# rc2014_nsc800.net
KiCad netlist of a schematic drawn in EAGLE
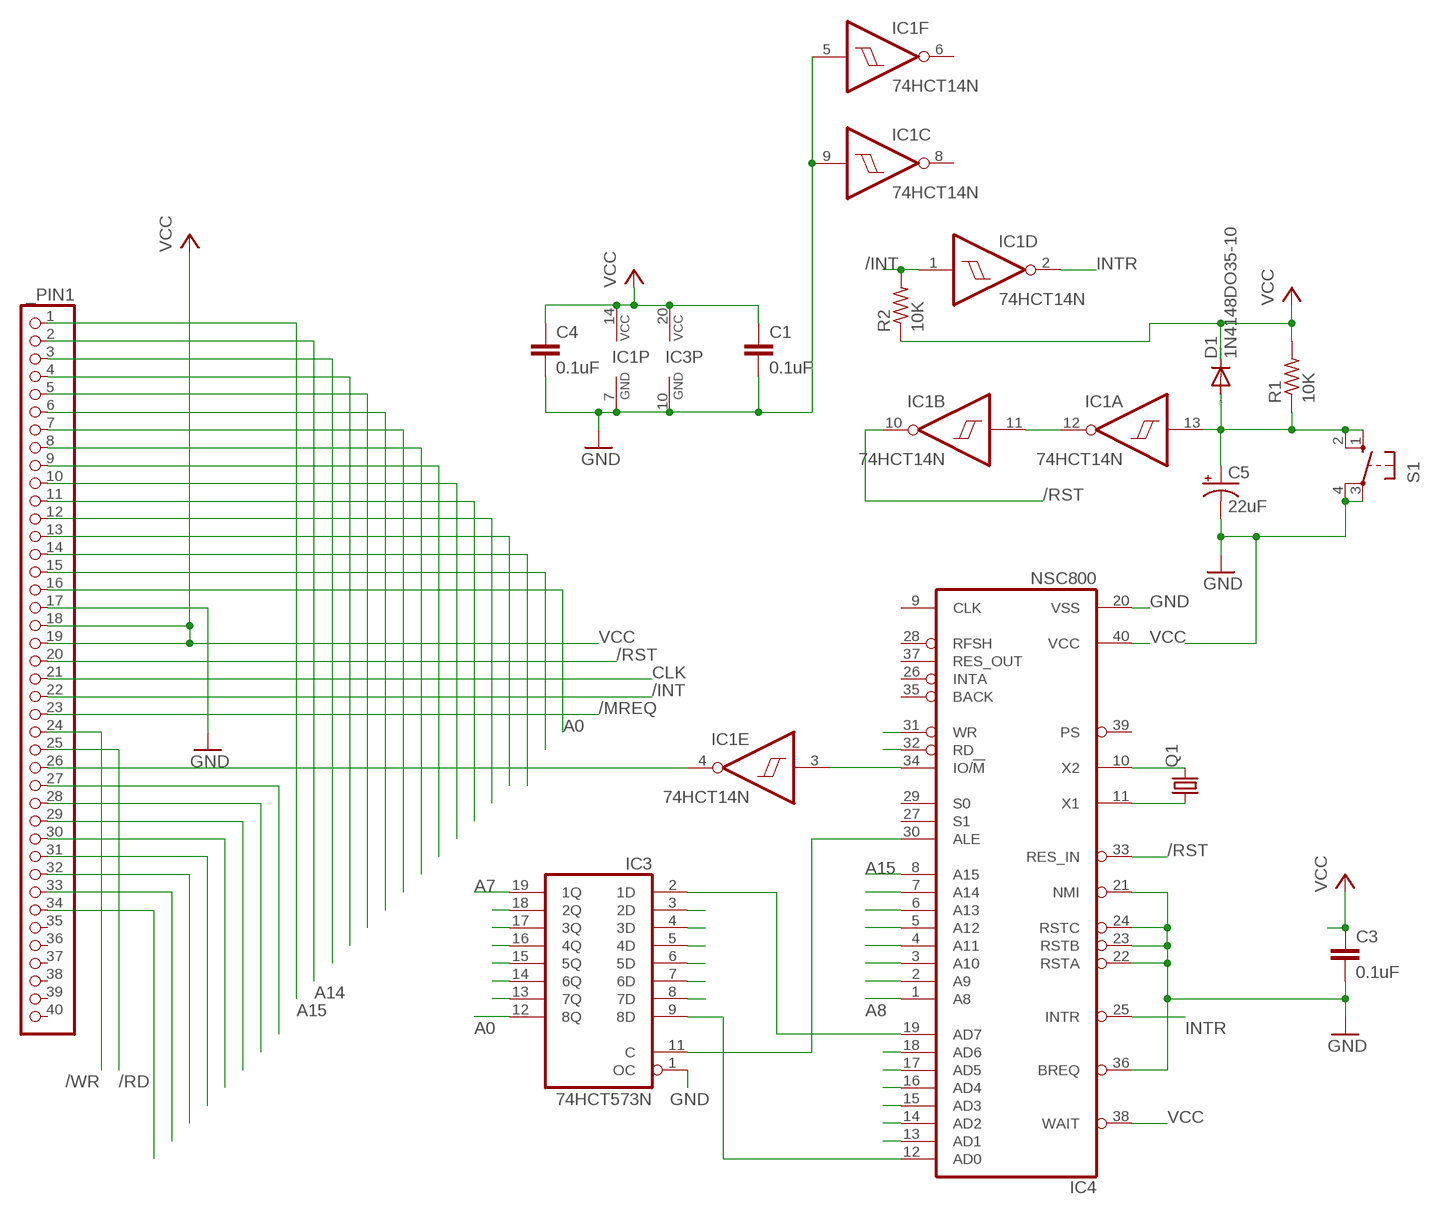
[diagram p0: schematic, sheet 1]

(export (version "E")
  (design (tool "Eeschema 10.0.6"))
  (components
    (comp (ref "C1")
      (value "0.1uF")
      (footprint "eagle-import:C050-024X044")
      (libsource (lib "eagle-import") (part "C-EU050-024X044"))
    )
    (comp (ref "C3")
      (value "0.1uF")
      (footprint "eagle-import:C050-024X044")
      (libsource (lib "eagle-import") (part "C-EU050-024X044"))
    )
    (comp (ref "C4")
      (value "0.1uF")
      (footprint "eagle-import:C050-024X044")
      (libsource (lib "eagle-import") (part "C-EU050-024X044"))
    )
    (comp (ref "C5")
      (value "22uF")
      (footprint "eagle-import:TAP5-80")
      (libsource (lib "eagle-import") (part "CPOL-USTAP5-80"))
    )
    (comp (ref "D1")
      (value "1N4148DO35-10")
      (footprint "eagle-import:DO35-10")
      (libsource (lib "eagle-import") (part "1N4148DO35-10"))
    )
    (comp (ref "IC1")
      (value "74HCT14N")
      (footprint "eagle-import:DIL14")
      (libsource (lib "eagle-import") (part "7414NHCT"))
    )
    (comp (ref "IC3")
      (value "74HCT573N")
      (footprint "eagle-import:DIL20")
      (libsource (lib "eagle-import") (part "74573NHCT"))
    )
    (comp (ref "IC4")
      (value "NSC800")
      (footprint "eagle-import:DIL40")
      (libsource (lib "eagle-import") (part "NSC800"))
    )
    (comp (ref "Q1")
      (value "CRYSTALHC49S")
      (footprint "eagle-import:HC49_S")
      (libsource (lib "eagle-import") (part "CRYSTALHC49S"))
    )
    (comp (ref "R1")
      (value "10K")
      (footprint "eagle-import:0207_10")
      (libsource (lib "eagle-import") (part "R-US_0207/10"))
    )
    (comp (ref "R2")
      (value "10K")
      (footprint "eagle-import:0207_10")
      (libsource (lib "eagle-import") (part "R-US_0207/10"))
    )
    (comp (ref "S1")
      (value "10-XX")
      (footprint "eagle-import:B3F-10XX")
      (fields (field (name "MPN") "B3F-1000"))
      (libsource (lib "eagle-import") (part "10-XX"))
    )
    (comp (ref "_PIN1")
      (value "PINHD-1X40")
      (footprint "eagle-import:1X40")
      (libsource (lib "eagle-import") (part "PINHD-1X40"))
    )
  )
  (nets
    (net (code "1") (name "/A0") (class "Default")
      (node (ref "IC3") (pin "12") (pinfunction "8Q_12") (pintype "tri_state"))
      (node (ref "_PIN1") (pin "16") (pinfunction "16_16") (pintype "passive"))
    )
    (net (code "2") (name "/A1") (class "Default")
      (node (ref "IC3") (pin "13") (pinfunction "7Q_13") (pintype "tri_state"))
      (node (ref "_PIN1") (pin "15") (pinfunction "15_15") (pintype "passive"))
    )
    (net (code "3") (name "/A2") (class "Default")
      (node (ref "IC3") (pin "14") (pinfunction "6Q_14") (pintype "tri_state"))
      (node (ref "_PIN1") (pin "14") (pinfunction "14_14") (pintype "passive"))
    )
    (net (code "4") (name "/A3") (class "Default")
      (node (ref "IC3") (pin "15") (pinfunction "5Q_15") (pintype "tri_state"))
      (node (ref "_PIN1") (pin "13") (pinfunction "13_13") (pintype "passive"))
    )
    (net (code "5") (name "/A4") (class "Default")
      (node (ref "IC3") (pin "16") (pinfunction "4Q_16") (pintype "tri_state"))
      (node (ref "_PIN1") (pin "12") (pinfunction "12_12") (pintype "passive"))
    )
    (net (code "6") (name "/A5") (class "Default")
      (node (ref "IC3") (pin "17") (pinfunction "3Q_17") (pintype "tri_state"))
      (node (ref "_PIN1") (pin "11") (pinfunction "11_11") (pintype "passive"))
    )
    (net (code "7") (name "/A6") (class "Default")
      (node (ref "IC3") (pin "18") (pinfunction "2Q_18") (pintype "tri_state"))
      (node (ref "_PIN1") (pin "10") (pinfunction "10_10") (pintype "passive"))
    )
    (net (code "8") (name "/A7") (class "Default")
      (node (ref "IC3") (pin "19") (pinfunction "1Q_19") (pintype "tri_state"))
      (node (ref "_PIN1") (pin "9") (pinfunction "9_9") (pintype "passive"))
    )
    (net (code "9") (name "/A8") (class "Default")
      (node (ref "IC4") (pin "1") (pinfunction "A8_1") (pintype "output"))
      (node (ref "_PIN1") (pin "8") (pinfunction "8_8") (pintype "passive"))
    )
    (net (code "10") (name "/A9") (class "Default")
      (node (ref "IC4") (pin "2") (pinfunction "A9_2") (pintype "output"))
      (node (ref "_PIN1") (pin "7") (pinfunction "7_7") (pintype "passive"))
    )
    (net (code "11") (name "/A10") (class "Default")
      (node (ref "IC4") (pin "3") (pinfunction "A10_3") (pintype "output"))
      (node (ref "_PIN1") (pin "6") (pinfunction "6_6") (pintype "passive"))
    )
    (net (code "12") (name "/A11") (class "Default")
      (node (ref "IC4") (pin "4") (pinfunction "A11_4") (pintype "output"))
      (node (ref "_PIN1") (pin "5") (pinfunction "5_5") (pintype "passive"))
    )
    (net (code "13") (name "/A12") (class "Default")
      (node (ref "IC4") (pin "5") (pinfunction "A12_5") (pintype "output"))
      (node (ref "_PIN1") (pin "4") (pinfunction "4_4") (pintype "passive"))
    )
    (net (code "14") (name "/A13") (class "Default")
      (node (ref "IC4") (pin "6") (pinfunction "A13_6") (pintype "output"))
      (node (ref "_PIN1") (pin "3") (pinfunction "3_3") (pintype "passive"))
    )
    (net (code "15") (name "/A14") (class "Default")
      (node (ref "IC4") (pin "7") (pinfunction "A14_7") (pintype "output"))
      (node (ref "_PIN1") (pin "2") (pinfunction "2_2") (pintype "passive"))
    )
    (net (code "16") (name "/A15") (class "Default")
      (node (ref "IC4") (pin "8") (pinfunction "A15_8") (pintype "output"))
      (node (ref "_PIN1") (pin "1") (pinfunction "1_1") (pintype "passive"))
    )
    (net (code "17") (name "/CLK") (class "Default")
      (node (ref "_PIN1") (pin "21") (pinfunction "21_21") (pintype "passive"))
    )
    (net (code "18") (name "/D0") (class "Default")
      (node (ref "IC3") (pin "9") (pinfunction "8D_9") (pintype "input"))
      (node (ref "IC4") (pin "12") (pinfunction "AD0_12") (pintype "bidirectional"))
      (node (ref "_PIN1") (pin "27") (pinfunction "27_27") (pintype "passive"))
    )
    (net (code "19") (name "/D1") (class "Default")
      (node (ref "IC3") (pin "8") (pinfunction "7D_8") (pintype "input"))
      (node (ref "IC4") (pin "13") (pinfunction "AD1_13") (pintype "bidirectional"))
      (node (ref "_PIN1") (pin "28") (pinfunction "28_28") (pintype "passive"))
    )
    (net (code "20") (name "/D2") (class "Default")
      (node (ref "IC3") (pin "7") (pinfunction "6D_7") (pintype "input"))
      (node (ref "IC4") (pin "14") (pinfunction "AD2_14") (pintype "bidirectional"))
      (node (ref "_PIN1") (pin "29") (pinfunction "29_29") (pintype "passive"))
    )
    (net (code "21") (name "/D3") (class "Default")
      (node (ref "IC3") (pin "6") (pinfunction "5D_6") (pintype "input"))
      (node (ref "IC4") (pin "15") (pinfunction "AD3_15") (pintype "bidirectional"))
      (node (ref "_PIN1") (pin "30") (pinfunction "30_30") (pintype "passive"))
    )
    (net (code "22") (name "/D4") (class "Default")
      (node (ref "IC3") (pin "5") (pinfunction "4D_5") (pintype "input"))
      (node (ref "IC4") (pin "16") (pinfunction "AD4_16") (pintype "bidirectional"))
      (node (ref "_PIN1") (pin "31") (pinfunction "31_31") (pintype "passive"))
    )
    (net (code "23") (name "/D5") (class "Default")
      (node (ref "IC3") (pin "4") (pinfunction "3D_4") (pintype "input"))
      (node (ref "IC4") (pin "17") (pinfunction "AD5_17") (pintype "bidirectional"))
      (node (ref "_PIN1") (pin "32") (pinfunction "32_32") (pintype "passive"))
    )
    (net (code "24") (name "/D6") (class "Default")
      (node (ref "IC3") (pin "3") (pinfunction "2D_3") (pintype "input"))
      (node (ref "IC4") (pin "18") (pinfunction "AD6_18") (pintype "bidirectional"))
      (node (ref "_PIN1") (pin "33") (pinfunction "33_33") (pintype "passive"))
    )
    (net (code "25") (name "/D7") (class "Default")
      (node (ref "IC3") (pin "2") (pinfunction "1D_2") (pintype "input"))
      (node (ref "IC4") (pin "19") (pinfunction "AD7_19") (pintype "bidirectional"))
      (node (ref "_PIN1") (pin "34") (pinfunction "34_34") (pintype "passive"))
    )
    (net (code "26") (name "/INTR") (class "Default")
      (node (ref "IC1") (pin "2") (pinfunction "O_2") (pintype "output"))
      (node (ref "IC4") (pin "25") (pinfunction "INTR_25") (pintype "input"))
    )
    (net (code "27") (name "/{slash}INT") (class "Default")
      (node (ref "IC1") (pin "1") (pinfunction "I_1") (pintype "input"))
      (node (ref "R2") (pin "2") (pinfunction "2_2") (pintype "passive"))
      (node (ref "_PIN1") (pin "22") (pinfunction "22_22") (pintype "passive"))
    )
    (net (code "28") (name "/{slash}MREQ") (class "Default")
      (node (ref "IC1") (pin "3") (pinfunction "I_3") (pintype "input"))
      (node (ref "IC4") (pin "34") (pinfunction "IO/~{M}_34") (pintype "output"))
      (node (ref "_PIN1") (pin "23") (pinfunction "23_23") (pintype "passive"))
    )
    (net (code "29") (name "/{slash}RD") (class "Default")
      (node (ref "IC4") (pin "32") (pinfunction "RD_32") (pintype "output"))
      (node (ref "_PIN1") (pin "25") (pinfunction "25_25") (pintype "passive"))
    )
    (net (code "30") (name "/{slash}RST") (class "Default")
      (node (ref "IC1") (pin "10") (pinfunction "O_10") (pintype "output"))
      (node (ref "IC4") (pin "33") (pinfunction "RES_IN_33") (pintype "input"))
      (node (ref "_PIN1") (pin "20") (pinfunction "20_20") (pintype "passive"))
    )
    (net (code "31") (name "/{slash}WR") (class "Default")
      (node (ref "IC4") (pin "31") (pinfunction "WR_31") (pintype "output"))
      (node (ref "_PIN1") (pin "24") (pinfunction "24_24") (pintype "passive"))
    )
    (net (code "32") (name "GND") (class "Default")
      (node (ref "C1") (pin "2") (pinfunction "2_2") (pintype "passive"))
      (node (ref "C3") (pin "2") (pinfunction "2_2") (pintype "passive"))
      (node (ref "C4") (pin "2") (pinfunction "2_2") (pintype "passive"))
      (node (ref "C5") (pin "-") (pinfunction "-_-") (pintype "passive"))
      (node (ref "IC1") (pin "5") (pinfunction "I_5") (pintype "input"))
      (node (ref "IC1") (pin "7") (pinfunction "GND_7") (pintype "power_in"))
      (node (ref "IC1") (pin "9") (pinfunction "I_9") (pintype "input"))
      (node (ref "IC3") (pin "1") (pinfunction "OC_1") (pintype "input"))
      (node (ref "IC3") (pin "10") (pinfunction "GND_10") (pintype "power_in"))
      (node (ref "IC4") (pin "20") (pinfunction "VSS_20") (pintype "power_in"))
      (node (ref "IC4") (pin "21") (pinfunction "NMI_21") (pintype "input"))
      (node (ref "IC4") (pin "22") (pinfunction "RSTA_22") (pintype "input"))
      (node (ref "IC4") (pin "23") (pinfunction "RSTB_23") (pintype "input"))
      (node (ref "IC4") (pin "24") (pinfunction "RSTC_24") (pintype "input"))
      (node (ref "IC4") (pin "36") (pinfunction "BREQ_36") (pintype "input"))
      (node (ref "S1") (pin "3") (pinfunction "P_3") (pintype "passive"))
      (node (ref "S1") (pin "4") (pinfunction "P1_4") (pintype "passive"))
      (node (ref "_PIN1") (pin "17") (pinfunction "17_17") (pintype "passive"))
    )
    (net (code "33") (name "Net-(IC1A-I)") (class "Default")
      (node (ref "C5") (pin "+") (pinfunction "+_+") (pintype "passive"))
      (node (ref "D1") (pin "A") (pinfunction "A_A") (pintype "passive"))
      (node (ref "IC1") (pin "13") (pinfunction "I_13") (pintype "input"))
      (node (ref "R1") (pin "1") (pinfunction "1_1") (pintype "passive"))
      (node (ref "S1") (pin "1") (pinfunction "S_1") (pintype "passive"))
      (node (ref "S1") (pin "2") (pinfunction "S1_2") (pintype "passive"))
    )
    (net (code "34") (name "Net-(IC1A-O)") (class "Default")
      (node (ref "IC1") (pin "11") (pinfunction "I_11") (pintype "input"))
      (node (ref "IC1") (pin "12") (pinfunction "O_12") (pintype "output"))
    )
    (net (code "35") (name "Net-(IC1E-O)") (class "Default")
      (node (ref "IC1") (pin "4") (pinfunction "O_4") (pintype "output"))
      (node (ref "_PIN1") (pin "26") (pinfunction "26_26") (pintype "passive"))
    )
    (net (code "36") (name "Net-(IC3A-C)") (class "Default")
      (node (ref "IC3") (pin "11") (pinfunction "C_11") (pintype "input"))
      (node (ref "IC4") (pin "30") (pinfunction "ALE_30") (pintype "output"))
    )
    (net (code "37") (name "Net-(IC4-X1)") (class "Default")
      (node (ref "IC4") (pin "11") (pinfunction "X1_11") (pintype "input"))
      (node (ref "Q1") (pin "1") (pinfunction "1_1") (pintype "passive"))
    )
    (net (code "38") (name "Net-(IC4-X2)") (class "Default")
      (node (ref "IC4") (pin "10") (pinfunction "X2_10") (pintype "input"))
      (node (ref "Q1") (pin "2") (pinfunction "2_2") (pintype "passive"))
    )
    (net (code "39") (name "VCC") (class "Default")
      (node (ref "C1") (pin "1") (pinfunction "1_1") (pintype "passive"))
      (node (ref "C3") (pin "1") (pinfunction "1_1") (pintype "passive"))
      (node (ref "C4") (pin "1") (pinfunction "1_1") (pintype "passive"))
      (node (ref "D1") (pin "C") (pinfunction "C_C") (pintype "passive"))
      (node (ref "IC1") (pin "14") (pinfunction "VCC_14") (pintype "power_in"))
      (node (ref "IC3") (pin "20") (pinfunction "VCC_20") (pintype "power_in"))
      (node (ref "IC4") (pin "38") (pinfunction "WAIT_38") (pintype "input"))
      (node (ref "IC4") (pin "40") (pinfunction "VCC_40") (pintype "power_in"))
      (node (ref "R1") (pin "2") (pinfunction "2_2") (pintype "passive"))
      (node (ref "R2") (pin "1") (pinfunction "1_1") (pintype "passive"))
      (node (ref "_PIN1") (pin "18") (pinfunction "18_18") (pintype "passive"))
      (node (ref "_PIN1") (pin "19") (pinfunction "19_19") (pintype "passive"))
    )
    (net (code "40") (name "unconnected-(IC1C-O-Pad8)") (class "Default")
      (node (ref "IC1") (pin "8") (pinfunction "O_8") (pintype "output"))
    )
    (net (code "41") (name "unconnected-(IC1F-O-Pad6)") (class "Default")
      (node (ref "IC1") (pin "6") (pinfunction "O_6") (pintype "output"))
    )
    (net (code "42") (name "unconnected-(IC4-BACK-Pad35)") (class "Default")
      (node (ref "IC4") (pin "35") (pinfunction "BACK_35") (pintype "output"))
    )
    (net (code "43") (name "unconnected-(IC4-CLK-Pad9)") (class "Default")
      (node (ref "IC4") (pin "9") (pinfunction "CLK_9") (pintype "output"))
    )
    (net (code "44") (name "unconnected-(IC4-INTA-Pad26)") (class "Default")
      (node (ref "IC4") (pin "26") (pinfunction "INTA_26") (pintype "output"))
    )
    (net (code "45") (name "unconnected-(IC4-PS-Pad39)") (class "Default")
      (node (ref "IC4") (pin "39") (pinfunction "PS_39") (pintype "input"))
    )
    (net (code "46") (name "unconnected-(IC4-RES_OUT-Pad37)") (class "Default")
      (node (ref "IC4") (pin "37") (pinfunction "RES_OUT_37") (pintype "output"))
    )
    (net (code "47") (name "unconnected-(IC4-RFSH-Pad28)") (class "Default")
      (node (ref "IC4") (pin "28") (pinfunction "RFSH_28") (pintype "output"))
    )
    (net (code "48") (name "unconnected-(IC4-S0-Pad29)") (class "Default")
      (node (ref "IC4") (pin "29") (pinfunction "S0_29") (pintype "output"))
    )
    (net (code "49") (name "unconnected-(IC4-S1-Pad27)") (class "Default")
      (node (ref "IC4") (pin "27") (pinfunction "S1_27") (pintype "output"))
    )
    (net (code "50") (name "unconnected-(_PIN1-Pad35)") (class "Default")
      (node (ref "_PIN1") (pin "35") (pinfunction "35_35") (pintype "passive"))
    )
    (net (code "51") (name "unconnected-(_PIN1-Pad36)") (class "Default")
      (node (ref "_PIN1") (pin "36") (pinfunction "36_36") (pintype "passive"))
    )
    (net (code "52") (name "unconnected-(_PIN1-Pad37)") (class "Default")
      (node (ref "_PIN1") (pin "37") (pinfunction "37_37") (pintype "passive"))
    )
    (net (code "53") (name "unconnected-(_PIN1-Pad38)") (class "Default")
      (node (ref "_PIN1") (pin "38") (pinfunction "38_38") (pintype "passive"))
    )
    (net (code "54") (name "unconnected-(_PIN1-Pad39)") (class "Default")
      (node (ref "_PIN1") (pin "39") (pinfunction "39_39") (pintype "passive"))
    )
    (net (code "55") (name "unconnected-(_PIN1-Pad40)") (class "Default")
      (node (ref "_PIN1") (pin "40") (pinfunction "40_40") (pintype "passive"))
    )
  )
)
